# Board_Jam_v2.net
KiCad netlist of a schematic drawn in EAGLE
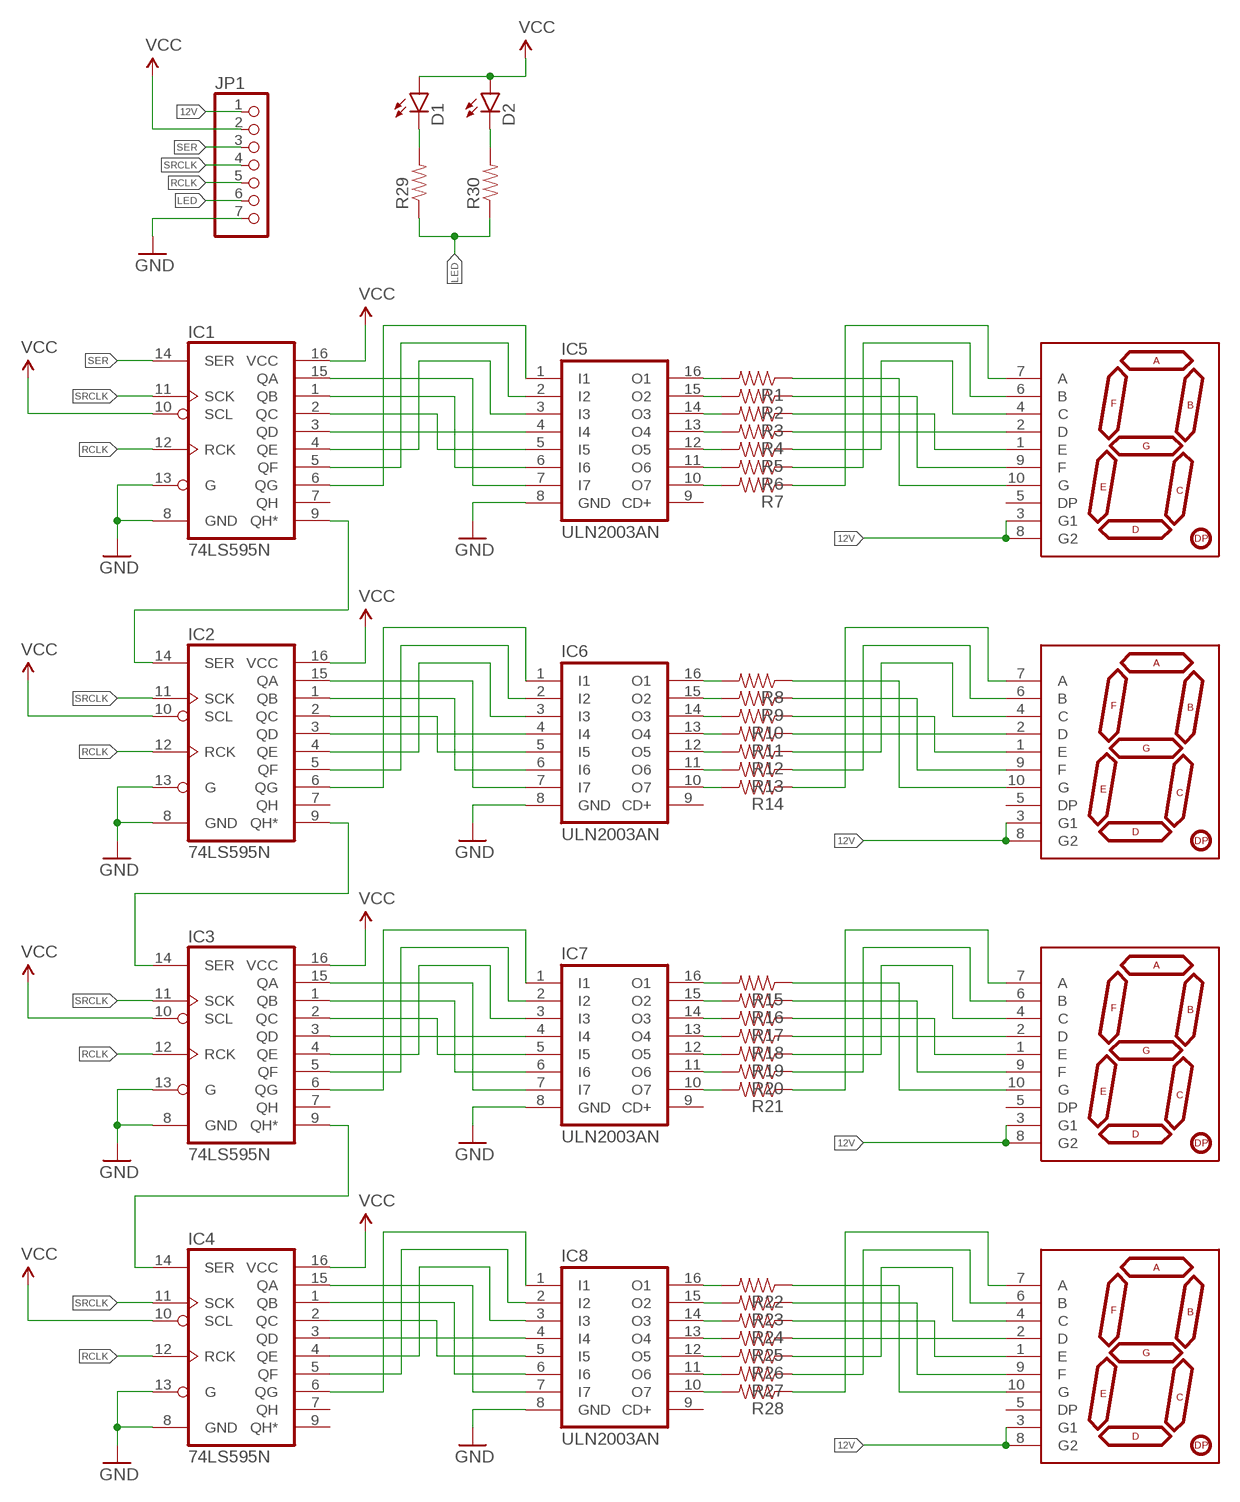
[diagram p0: schematic, sheet 1]

(export (version "E")
  (design (tool "Eeschema 10.0.6"))
  (components
    (comp (ref "D1")
      (value "LED5MM")
      (footprint "eagle-import:LED5MM")
      (libsource (lib "eagle-import") (part "LED5MM"))
    )
    (comp (ref "D2")
      (value "LED5MM")
      (footprint "eagle-import:LED5MM")
      (libsource (lib "eagle-import") (part "LED5MM"))
    )
    (comp (ref "IC1")
      (value "74LS595N")
      (footprint "eagle-import:DIL16")
      (libsource (lib "eagle-import") (part "74595NLS"))
    )
    (comp (ref "IC2")
      (value "74LS595N")
      (footprint "eagle-import:DIL16")
      (libsource (lib "eagle-import") (part "74595NLS"))
    )
    (comp (ref "IC3")
      (value "74LS595N")
      (footprint "eagle-import:DIL16")
      (libsource (lib "eagle-import") (part "74595NLS"))
    )
    (comp (ref "IC4")
      (value "74LS595N")
      (footprint "eagle-import:DIL16")
      (libsource (lib "eagle-import") (part "74595NLS"))
    )
    (comp (ref "IC5")
      (value "ULN2003AN")
      (footprint "eagle-import:DIL16")
      (libsource (lib "eagle-import") (part "ULN2003AN"))
    )
    (comp (ref "IC6")
      (value "ULN2003AN")
      (footprint "eagle-import:DIL16")
      (libsource (lib "eagle-import") (part "ULN2003AN"))
    )
    (comp (ref "IC7")
      (value "ULN2003AN")
      (footprint "eagle-import:DIL16")
      (libsource (lib "eagle-import") (part "ULN2003AN"))
    )
    (comp (ref "IC8")
      (value "ULN2003AN")
      (footprint "eagle-import:DIL16")
      (libsource (lib "eagle-import") (part "ULN2003AN"))
    )
    (comp (ref "JP1")
      (value "PINHD-1X7")
      (footprint "eagle-import:1X07")
      (libsource (lib "eagle-import") (part "PINHD-1X7"))
    )
    (comp (ref "R1")
      (value "RESISTORPTH-1/4W")
      (footprint "eagle-import:AXIAL-0.4")
      (libsource (lib "eagle-import") (part "RESISTORPTH-1/4W"))
    )
    (comp (ref "R2")
      (value "RESISTORPTH-1/4W")
      (footprint "eagle-import:AXIAL-0.4")
      (libsource (lib "eagle-import") (part "RESISTORPTH-1/4W"))
    )
    (comp (ref "R3")
      (value "RESISTORPTH-1/4W")
      (footprint "eagle-import:AXIAL-0.4")
      (libsource (lib "eagle-import") (part "RESISTORPTH-1/4W"))
    )
    (comp (ref "R4")
      (value "RESISTORPTH-1/4W")
      (footprint "eagle-import:AXIAL-0.4")
      (libsource (lib "eagle-import") (part "RESISTORPTH-1/4W"))
    )
    (comp (ref "R5")
      (value "RESISTORPTH-1/4W")
      (footprint "eagle-import:AXIAL-0.4")
      (libsource (lib "eagle-import") (part "RESISTORPTH-1/4W"))
    )
    (comp (ref "R6")
      (value "RESISTORPTH-1/4W")
      (footprint "eagle-import:AXIAL-0.4")
      (libsource (lib "eagle-import") (part "RESISTORPTH-1/4W"))
    )
    (comp (ref "R7")
      (value "RESISTORPTH-1/4W")
      (footprint "eagle-import:AXIAL-0.4")
      (libsource (lib "eagle-import") (part "RESISTORPTH-1/4W"))
    )
    (comp (ref "R8")
      (value "RESISTORPTH-1/4W")
      (footprint "eagle-import:AXIAL-0.4")
      (libsource (lib "eagle-import") (part "RESISTORPTH-1/4W"))
    )
    (comp (ref "R9")
      (value "RESISTORPTH-1/4W")
      (footprint "eagle-import:AXIAL-0.4")
      (libsource (lib "eagle-import") (part "RESISTORPTH-1/4W"))
    )
    (comp (ref "R10")
      (value "RESISTORPTH-1/4W")
      (footprint "eagle-import:AXIAL-0.4")
      (libsource (lib "eagle-import") (part "RESISTORPTH-1/4W"))
    )
    (comp (ref "R11")
      (value "RESISTORPTH-1/4W")
      (footprint "eagle-import:AXIAL-0.4")
      (libsource (lib "eagle-import") (part "RESISTORPTH-1/4W"))
    )
    (comp (ref "R12")
      (value "RESISTORPTH-1/4W")
      (footprint "eagle-import:AXIAL-0.4")
      (libsource (lib "eagle-import") (part "RESISTORPTH-1/4W"))
    )
    (comp (ref "R13")
      (value "RESISTORPTH-1/4W")
      (footprint "eagle-import:AXIAL-0.4")
      (libsource (lib "eagle-import") (part "RESISTORPTH-1/4W"))
    )
    (comp (ref "R14")
      (value "RESISTORPTH-1/4W")
      (footprint "eagle-import:AXIAL-0.4")
      (libsource (lib "eagle-import") (part "RESISTORPTH-1/4W"))
    )
    (comp (ref "R15")
      (value "RESISTORPTH-1/4W")
      (footprint "eagle-import:AXIAL-0.4")
      (libsource (lib "eagle-import") (part "RESISTORPTH-1/4W"))
    )
    (comp (ref "R16")
      (value "RESISTORPTH-1/4W")
      (footprint "eagle-import:AXIAL-0.4")
      (libsource (lib "eagle-import") (part "RESISTORPTH-1/4W"))
    )
    (comp (ref "R17")
      (value "RESISTORPTH-1/4W")
      (footprint "eagle-import:AXIAL-0.4")
      (libsource (lib "eagle-import") (part "RESISTORPTH-1/4W"))
    )
    (comp (ref "R18")
      (value "RESISTORPTH-1/4W")
      (footprint "eagle-import:AXIAL-0.4")
      (libsource (lib "eagle-import") (part "RESISTORPTH-1/4W"))
    )
    (comp (ref "R19")
      (value "RESISTORPTH-1/4W")
      (footprint "eagle-import:AXIAL-0.4")
      (libsource (lib "eagle-import") (part "RESISTORPTH-1/4W"))
    )
    (comp (ref "R20")
      (value "RESISTORPTH-1/4W")
      (footprint "eagle-import:AXIAL-0.4")
      (libsource (lib "eagle-import") (part "RESISTORPTH-1/4W"))
    )
    (comp (ref "R21")
      (value "RESISTORPTH-1/4W")
      (footprint "eagle-import:AXIAL-0.4")
      (libsource (lib "eagle-import") (part "RESISTORPTH-1/4W"))
    )
    (comp (ref "R22")
      (value "RESISTORPTH-1/4W")
      (footprint "eagle-import:AXIAL-0.4")
      (libsource (lib "eagle-import") (part "RESISTORPTH-1/4W"))
    )
    (comp (ref "R23")
      (value "RESISTORPTH-1/4W")
      (footprint "eagle-import:AXIAL-0.4")
      (libsource (lib "eagle-import") (part "RESISTORPTH-1/4W"))
    )
    (comp (ref "R24")
      (value "RESISTORPTH-1/4W")
      (footprint "eagle-import:AXIAL-0.4")
      (libsource (lib "eagle-import") (part "RESISTORPTH-1/4W"))
    )
    (comp (ref "R25")
      (value "RESISTORPTH-1/4W")
      (footprint "eagle-import:AXIAL-0.4")
      (libsource (lib "eagle-import") (part "RESISTORPTH-1/4W"))
    )
    (comp (ref "R26")
      (value "RESISTORPTH-1/4W")
      (footprint "eagle-import:AXIAL-0.4")
      (libsource (lib "eagle-import") (part "RESISTORPTH-1/4W"))
    )
    (comp (ref "R27")
      (value "RESISTORPTH-1/4W")
      (footprint "eagle-import:AXIAL-0.4")
      (libsource (lib "eagle-import") (part "RESISTORPTH-1/4W"))
    )
    (comp (ref "R28")
      (value "RESISTORPTH-1/4W")
      (footprint "eagle-import:AXIAL-0.4")
      (libsource (lib "eagle-import") (part "RESISTORPTH-1/4W"))
    )
    (comp (ref "R29")
      (value "RESISTORPTH-1/4W")
      (footprint "eagle-import:AXIAL-0.4")
      (libsource (lib "eagle-import") (part "RESISTORPTH-1/4W"))
    )
    (comp (ref "R30")
      (value "RESISTORPTH-1/4W")
      (footprint "eagle-import:AXIAL-0.4")
      (libsource (lib "eagle-import") (part "RESISTORPTH-1/4W"))
    )
    (comp (ref "U$1")
      (value "7-SEGMENT-DISPLAY-1\"-RED7-SEGMENT-1.8\"PTH")
      (footprint "eagle-import:7-SEGMENT-1_PTH")
      (libsource (lib "eagle-import") (part "7-SEGMENT-DISPLAY-1{dblquote}-RED7-SEGMENT-1.8{dblquote}PTH"))
    )
    (comp (ref "U$2")
      (value "7-SEGMENT-DISPLAY-1\"-RED7-SEGMENT-1.8\"PTH")
      (footprint "eagle-import:7-SEGMENT-1_PTH")
      (libsource (lib "eagle-import") (part "7-SEGMENT-DISPLAY-1{dblquote}-RED7-SEGMENT-1.8{dblquote}PTH"))
    )
    (comp (ref "U$3")
      (value "7-SEGMENT-DISPLAY-1\"-RED7-SEGMENT-1.8\"PTH")
      (footprint "eagle-import:7-SEGMENT-1_PTH")
      (libsource (lib "eagle-import") (part "7-SEGMENT-DISPLAY-1{dblquote}-RED7-SEGMENT-1.8{dblquote}PTH"))
    )
    (comp (ref "U$4")
      (value "7-SEGMENT-DISPLAY-1\"-RED7-SEGMENT-1.8\"PTH")
      (footprint "eagle-import:7-SEGMENT-1_PTH")
      (libsource (lib "eagle-import") (part "7-SEGMENT-DISPLAY-1{dblquote}-RED7-SEGMENT-1.8{dblquote}PTH"))
    )
  )
  (nets
    (net (code "1") (name "12V") (class "Default")
      (node (ref "JP1") (pin "1") (pinfunction "1_1") (pintype "passive"))
      (node (ref "U$1") (pin "3") (pinfunction "G1_3") (pintype "bidirectional"))
      (node (ref "U$1") (pin "8") (pinfunction "G2_8") (pintype "bidirectional"))
      (node (ref "U$2") (pin "3") (pinfunction "G1_3") (pintype "bidirectional"))
      (node (ref "U$2") (pin "8") (pinfunction "G2_8") (pintype "bidirectional"))
      (node (ref "U$3") (pin "3") (pinfunction "G1_3") (pintype "bidirectional"))
      (node (ref "U$3") (pin "8") (pinfunction "G2_8") (pintype "bidirectional"))
      (node (ref "U$4") (pin "3") (pinfunction "G1_3") (pintype "bidirectional"))
      (node (ref "U$4") (pin "8") (pinfunction "G2_8") (pintype "bidirectional"))
    )
    (net (code "2") (name "GND") (class "Default")
      (node (ref "IC1") (pin "13") (pinfunction "G_13") (pintype "input"))
      (node (ref "IC1") (pin "8") (pinfunction "GND_8") (pintype "power_in"))
      (node (ref "IC2") (pin "13") (pinfunction "G_13") (pintype "input"))
      (node (ref "IC2") (pin "8") (pinfunction "GND_8") (pintype "power_in"))
      (node (ref "IC3") (pin "13") (pinfunction "G_13") (pintype "input"))
      (node (ref "IC3") (pin "8") (pinfunction "GND_8") (pintype "power_in"))
      (node (ref "IC4") (pin "13") (pinfunction "G_13") (pintype "input"))
      (node (ref "IC4") (pin "8") (pinfunction "GND_8") (pintype "power_in"))
      (node (ref "IC5") (pin "8") (pinfunction "GND_8") (pintype "power_in"))
      (node (ref "IC6") (pin "8") (pinfunction "GND_8") (pintype "power_in"))
      (node (ref "IC7") (pin "8") (pinfunction "GND_8") (pintype "power_in"))
      (node (ref "IC8") (pin "8") (pinfunction "GND_8") (pintype "power_in"))
      (node (ref "JP1") (pin "7") (pinfunction "7_7") (pintype "passive"))
    )
    (net (code "3") (name "LED") (class "Default")
      (node (ref "JP1") (pin "6") (pinfunction "6_6") (pintype "passive"))
      (node (ref "R29") (pin "P$1") (pinfunction "1_P$1") (pintype "passive"))
      (node (ref "R30") (pin "P$1") (pinfunction "1_P$1") (pintype "passive"))
    )
    (net (code "4") (name "Net-(D1-C)") (class "Default")
      (node (ref "D1") (pin "K") (pinfunction "C_K") (pintype "passive"))
      (node (ref "R29") (pin "P$2") (pinfunction "2_P$2") (pintype "passive"))
    )
    (net (code "5") (name "Net-(D2-C)") (class "Default")
      (node (ref "D2") (pin "K") (pinfunction "C_K") (pintype "passive"))
      (node (ref "R30") (pin "P$2") (pinfunction "2_P$2") (pintype "passive"))
    )
    (net (code "6") (name "Net-(IC1-QA)") (class "Default")
      (node (ref "IC1") (pin "15") (pinfunction "QA_15") (pintype "tri_state"))
      (node (ref "IC5") (pin "7") (pinfunction "I7_7") (pintype "input"))
    )
    (net (code "7") (name "Net-(IC1-QB)") (class "Default")
      (node (ref "IC1") (pin "1") (pinfunction "QB_1") (pintype "tri_state"))
      (node (ref "IC5") (pin "6") (pinfunction "I6_6") (pintype "input"))
    )
    (net (code "8") (name "Net-(IC1-QC)") (class "Default")
      (node (ref "IC1") (pin "2") (pinfunction "QC_2") (pintype "tri_state"))
      (node (ref "IC5") (pin "5") (pinfunction "I5_5") (pintype "input"))
    )
    (net (code "9") (name "Net-(IC1-QD)") (class "Default")
      (node (ref "IC1") (pin "3") (pinfunction "QD_3") (pintype "tri_state"))
      (node (ref "IC5") (pin "4") (pinfunction "I4_4") (pintype "input"))
    )
    (net (code "10") (name "Net-(IC1-QE)") (class "Default")
      (node (ref "IC1") (pin "4") (pinfunction "QE_4") (pintype "tri_state"))
      (node (ref "IC5") (pin "3") (pinfunction "I3_3") (pintype "input"))
    )
    (net (code "11") (name "Net-(IC1-QF)") (class "Default")
      (node (ref "IC1") (pin "5") (pinfunction "QF_5") (pintype "tri_state"))
      (node (ref "IC5") (pin "2") (pinfunction "I2_2") (pintype "input"))
    )
    (net (code "12") (name "Net-(IC1-QG)") (class "Default")
      (node (ref "IC1") (pin "6") (pinfunction "QG_6") (pintype "tri_state"))
      (node (ref "IC5") (pin "1") (pinfunction "I1_1") (pintype "input"))
    )
    (net (code "13") (name "Net-(IC1-QH*)") (class "Default")
      (node (ref "IC1") (pin "9") (pinfunction "QH*_9") (pintype "tri_state"))
      (node (ref "IC2") (pin "14") (pinfunction "SER_14") (pintype "input"))
    )
    (net (code "14") (name "Net-(IC2-QA)") (class "Default")
      (node (ref "IC2") (pin "15") (pinfunction "QA_15") (pintype "tri_state"))
      (node (ref "IC6") (pin "7") (pinfunction "I7_7") (pintype "input"))
    )
    (net (code "15") (name "Net-(IC2-QB)") (class "Default")
      (node (ref "IC2") (pin "1") (pinfunction "QB_1") (pintype "tri_state"))
      (node (ref "IC6") (pin "6") (pinfunction "I6_6") (pintype "input"))
    )
    (net (code "16") (name "Net-(IC2-QC)") (class "Default")
      (node (ref "IC2") (pin "2") (pinfunction "QC_2") (pintype "tri_state"))
      (node (ref "IC6") (pin "5") (pinfunction "I5_5") (pintype "input"))
    )
    (net (code "17") (name "Net-(IC2-QD)") (class "Default")
      (node (ref "IC2") (pin "3") (pinfunction "QD_3") (pintype "tri_state"))
      (node (ref "IC6") (pin "4") (pinfunction "I4_4") (pintype "input"))
    )
    (net (code "18") (name "Net-(IC2-QE)") (class "Default")
      (node (ref "IC2") (pin "4") (pinfunction "QE_4") (pintype "tri_state"))
      (node (ref "IC6") (pin "3") (pinfunction "I3_3") (pintype "input"))
    )
    (net (code "19") (name "Net-(IC2-QF)") (class "Default")
      (node (ref "IC2") (pin "5") (pinfunction "QF_5") (pintype "tri_state"))
      (node (ref "IC6") (pin "2") (pinfunction "I2_2") (pintype "input"))
    )
    (net (code "20") (name "Net-(IC2-QG)") (class "Default")
      (node (ref "IC2") (pin "6") (pinfunction "QG_6") (pintype "tri_state"))
      (node (ref "IC6") (pin "1") (pinfunction "I1_1") (pintype "input"))
    )
    (net (code "21") (name "Net-(IC2-QH*)") (class "Default")
      (node (ref "IC2") (pin "9") (pinfunction "QH*_9") (pintype "tri_state"))
      (node (ref "IC3") (pin "14") (pinfunction "SER_14") (pintype "input"))
    )
    (net (code "22") (name "Net-(IC3-QA)") (class "Default")
      (node (ref "IC3") (pin "15") (pinfunction "QA_15") (pintype "tri_state"))
      (node (ref "IC7") (pin "7") (pinfunction "I7_7") (pintype "input"))
    )
    (net (code "23") (name "Net-(IC3-QB)") (class "Default")
      (node (ref "IC3") (pin "1") (pinfunction "QB_1") (pintype "tri_state"))
      (node (ref "IC7") (pin "6") (pinfunction "I6_6") (pintype "input"))
    )
    (net (code "24") (name "Net-(IC3-QC)") (class "Default")
      (node (ref "IC3") (pin "2") (pinfunction "QC_2") (pintype "tri_state"))
      (node (ref "IC7") (pin "5") (pinfunction "I5_5") (pintype "input"))
    )
    (net (code "25") (name "Net-(IC3-QD)") (class "Default")
      (node (ref "IC3") (pin "3") (pinfunction "QD_3") (pintype "tri_state"))
      (node (ref "IC7") (pin "4") (pinfunction "I4_4") (pintype "input"))
    )
    (net (code "26") (name "Net-(IC3-QE)") (class "Default")
      (node (ref "IC3") (pin "4") (pinfunction "QE_4") (pintype "tri_state"))
      (node (ref "IC7") (pin "3") (pinfunction "I3_3") (pintype "input"))
    )
    (net (code "27") (name "Net-(IC3-QF)") (class "Default")
      (node (ref "IC3") (pin "5") (pinfunction "QF_5") (pintype "tri_state"))
      (node (ref "IC7") (pin "2") (pinfunction "I2_2") (pintype "input"))
    )
    (net (code "28") (name "Net-(IC3-QG)") (class "Default")
      (node (ref "IC3") (pin "6") (pinfunction "QG_6") (pintype "tri_state"))
      (node (ref "IC7") (pin "1") (pinfunction "I1_1") (pintype "input"))
    )
    (net (code "29") (name "Net-(IC3-QH*)") (class "Default")
      (node (ref "IC3") (pin "9") (pinfunction "QH*_9") (pintype "tri_state"))
      (node (ref "IC4") (pin "14") (pinfunction "SER_14") (pintype "input"))
    )
    (net (code "30") (name "Net-(IC4-QA)") (class "Default")
      (node (ref "IC4") (pin "15") (pinfunction "QA_15") (pintype "tri_state"))
      (node (ref "IC8") (pin "7") (pinfunction "I7_7") (pintype "input"))
    )
    (net (code "31") (name "Net-(IC4-QB)") (class "Default")
      (node (ref "IC4") (pin "1") (pinfunction "QB_1") (pintype "tri_state"))
      (node (ref "IC8") (pin "6") (pinfunction "I6_6") (pintype "input"))
    )
    (net (code "32") (name "Net-(IC4-QC)") (class "Default")
      (node (ref "IC4") (pin "2") (pinfunction "QC_2") (pintype "tri_state"))
      (node (ref "IC8") (pin "5") (pinfunction "I5_5") (pintype "input"))
    )
    (net (code "33") (name "Net-(IC4-QD)") (class "Default")
      (node (ref "IC4") (pin "3") (pinfunction "QD_3") (pintype "tri_state"))
      (node (ref "IC8") (pin "4") (pinfunction "I4_4") (pintype "input"))
    )
    (net (code "34") (name "Net-(IC4-QE)") (class "Default")
      (node (ref "IC4") (pin "4") (pinfunction "QE_4") (pintype "tri_state"))
      (node (ref "IC8") (pin "3") (pinfunction "I3_3") (pintype "input"))
    )
    (net (code "35") (name "Net-(IC4-QF)") (class "Default")
      (node (ref "IC4") (pin "5") (pinfunction "QF_5") (pintype "tri_state"))
      (node (ref "IC8") (pin "2") (pinfunction "I2_2") (pintype "input"))
    )
    (net (code "36") (name "Net-(IC4-QG)") (class "Default")
      (node (ref "IC4") (pin "6") (pinfunction "QG_6") (pintype "tri_state"))
      (node (ref "IC8") (pin "1") (pinfunction "I1_1") (pintype "input"))
    )
    (net (code "37") (name "Net-(IC5-O1)") (class "Default")
      (node (ref "IC5") (pin "16") (pinfunction "O1_16") (pintype "open_collector"))
      (node (ref "R1") (pin "P$2") (pinfunction "2_P$2") (pintype "passive"))
    )
    (net (code "38") (name "Net-(IC5-O2)") (class "Default")
      (node (ref "IC5") (pin "15") (pinfunction "O2_15") (pintype "open_collector"))
      (node (ref "R2") (pin "P$2") (pinfunction "2_P$2") (pintype "passive"))
    )
    (net (code "39") (name "Net-(IC5-O3)") (class "Default")
      (node (ref "IC5") (pin "14") (pinfunction "O3_14") (pintype "open_collector"))
      (node (ref "R3") (pin "P$2") (pinfunction "2_P$2") (pintype "passive"))
    )
    (net (code "40") (name "Net-(IC5-O4)") (class "Default")
      (node (ref "IC5") (pin "13") (pinfunction "O4_13") (pintype "open_collector"))
      (node (ref "R4") (pin "P$2") (pinfunction "2_P$2") (pintype "passive"))
    )
    (net (code "41") (name "Net-(IC5-O5)") (class "Default")
      (node (ref "IC5") (pin "12") (pinfunction "O5_12") (pintype "open_collector"))
      (node (ref "R5") (pin "P$2") (pinfunction "2_P$2") (pintype "passive"))
    )
    (net (code "42") (name "Net-(IC5-O6)") (class "Default")
      (node (ref "IC5") (pin "11") (pinfunction "O6_11") (pintype "open_collector"))
      (node (ref "R6") (pin "P$2") (pinfunction "2_P$2") (pintype "passive"))
    )
    (net (code "43") (name "Net-(IC5-O7)") (class "Default")
      (node (ref "IC5") (pin "10") (pinfunction "O7_10") (pintype "open_collector"))
      (node (ref "R7") (pin "P$2") (pinfunction "2_P$2") (pintype "passive"))
    )
    (net (code "44") (name "Net-(IC6-O1)") (class "Default")
      (node (ref "IC6") (pin "16") (pinfunction "O1_16") (pintype "open_collector"))
      (node (ref "R8") (pin "P$2") (pinfunction "2_P$2") (pintype "passive"))
    )
    (net (code "45") (name "Net-(IC6-O2)") (class "Default")
      (node (ref "IC6") (pin "15") (pinfunction "O2_15") (pintype "open_collector"))
      (node (ref "R9") (pin "P$2") (pinfunction "2_P$2") (pintype "passive"))
    )
    (net (code "46") (name "Net-(IC6-O3)") (class "Default")
      (node (ref "IC6") (pin "14") (pinfunction "O3_14") (pintype "open_collector"))
      (node (ref "R10") (pin "P$2") (pinfunction "2_P$2") (pintype "passive"))
    )
    (net (code "47") (name "Net-(IC6-O4)") (class "Default")
      (node (ref "IC6") (pin "13") (pinfunction "O4_13") (pintype "open_collector"))
      (node (ref "R11") (pin "P$2") (pinfunction "2_P$2") (pintype "passive"))
    )
    (net (code "48") (name "Net-(IC6-O5)") (class "Default")
      (node (ref "IC6") (pin "12") (pinfunction "O5_12") (pintype "open_collector"))
      (node (ref "R12") (pin "P$2") (pinfunction "2_P$2") (pintype "passive"))
    )
    (net (code "49") (name "Net-(IC6-O6)") (class "Default")
      (node (ref "IC6") (pin "11") (pinfunction "O6_11") (pintype "open_collector"))
      (node (ref "R13") (pin "P$2") (pinfunction "2_P$2") (pintype "passive"))
    )
    (net (code "50") (name "Net-(IC6-O7)") (class "Default")
      (node (ref "IC6") (pin "10") (pinfunction "O7_10") (pintype "open_collector"))
      (node (ref "R14") (pin "P$2") (pinfunction "2_P$2") (pintype "passive"))
    )
    (net (code "51") (name "Net-(IC7-O1)") (class "Default")
      (node (ref "IC7") (pin "16") (pinfunction "O1_16") (pintype "open_collector"))
      (node (ref "R15") (pin "P$2") (pinfunction "2_P$2") (pintype "passive"))
    )
    (net (code "52") (name "Net-(IC7-O2)") (class "Default")
      (node (ref "IC7") (pin "15") (pinfunction "O2_15") (pintype "open_collector"))
      (node (ref "R16") (pin "P$2") (pinfunction "2_P$2") (pintype "passive"))
    )
    (net (code "53") (name "Net-(IC7-O3)") (class "Default")
      (node (ref "IC7") (pin "14") (pinfunction "O3_14") (pintype "open_collector"))
      (node (ref "R17") (pin "P$2") (pinfunction "2_P$2") (pintype "passive"))
    )
    (net (code "54") (name "Net-(IC7-O4)") (class "Default")
      (node (ref "IC7") (pin "13") (pinfunction "O4_13") (pintype "open_collector"))
      (node (ref "R18") (pin "P$2") (pinfunction "2_P$2") (pintype "passive"))
    )
    (net (code "55") (name "Net-(IC7-O5)") (class "Default")
      (node (ref "IC7") (pin "12") (pinfunction "O5_12") (pintype "open_collector"))
      (node (ref "R19") (pin "P$2") (pinfunction "2_P$2") (pintype "passive"))
    )
    (net (code "56") (name "Net-(IC7-O6)") (class "Default")
      (node (ref "IC7") (pin "11") (pinfunction "O6_11") (pintype "open_collector"))
      (node (ref "R20") (pin "P$2") (pinfunction "2_P$2") (pintype "passive"))
    )
    (net (code "57") (name "Net-(IC7-O7)") (class "Default")
      (node (ref "IC7") (pin "10") (pinfunction "O7_10") (pintype "open_collector"))
      (node (ref "R21") (pin "P$2") (pinfunction "2_P$2") (pintype "passive"))
    )
    (net (code "58") (name "Net-(IC8-O1)") (class "Default")
      (node (ref "IC8") (pin "16") (pinfunction "O1_16") (pintype "open_collector"))
      (node (ref "R22") (pin "P$2") (pinfunction "2_P$2") (pintype "passive"))
    )
    (net (code "59") (name "Net-(IC8-O2)") (class "Default")
      (node (ref "IC8") (pin "15") (pinfunction "O2_15") (pintype "open_collector"))
      (node (ref "R23") (pin "P$2") (pinfunction "2_P$2") (pintype "passive"))
    )
    (net (code "60") (name "Net-(IC8-O3)") (class "Default")
      (node (ref "IC8") (pin "14") (pinfunction "O3_14") (pintype "open_collector"))
      (node (ref "R24") (pin "P$2") (pinfunction "2_P$2") (pintype "passive"))
    )
    (net (code "61") (name "Net-(IC8-O4)") (class "Default")
      (node (ref "IC8") (pin "13") (pinfunction "O4_13") (pintype "open_collector"))
      (node (ref "R25") (pin "P$2") (pinfunction "2_P$2") (pintype "passive"))
    )
    (net (code "62") (name "Net-(IC8-O5)") (class "Default")
      (node (ref "IC8") (pin "12") (pinfunction "O5_12") (pintype "open_collector"))
      (node (ref "R26") (pin "P$2") (pinfunction "2_P$2") (pintype "passive"))
    )
    (net (code "63") (name "Net-(IC8-O6)") (class "Default")
      (node (ref "IC8") (pin "11") (pinfunction "O6_11") (pintype "open_collector"))
      (node (ref "R27") (pin "P$2") (pinfunction "2_P$2") (pintype "passive"))
    )
    (net (code "64") (name "Net-(IC8-O7)") (class "Default")
      (node (ref "IC8") (pin "10") (pinfunction "O7_10") (pintype "open_collector"))
      (node (ref "R28") (pin "P$2") (pinfunction "2_P$2") (pintype "passive"))
    )
    (net (code "65") (name "Net-(R1-1)") (class "Default")
      (node (ref "R1") (pin "P$1") (pinfunction "1_P$1") (pintype "passive"))
      (node (ref "U$1") (pin "10") (pinfunction "G_10") (pintype "bidirectional"))
    )
    (net (code "66") (name "Net-(R2-1)") (class "Default")
      (node (ref "R2") (pin "P$1") (pinfunction "1_P$1") (pintype "passive"))
      (node (ref "U$1") (pin "9") (pinfunction "F_9") (pintype "bidirectional"))
    )
    (net (code "67") (name "Net-(R3-1)") (class "Default")
      (node (ref "R3") (pin "P$1") (pinfunction "1_P$1") (pintype "passive"))
      (node (ref "U$1") (pin "1") (pinfunction "E_1") (pintype "bidirectional"))
    )
    (net (code "68") (name "Net-(R4-1)") (class "Default")
      (node (ref "R4") (pin "P$1") (pinfunction "1_P$1") (pintype "passive"))
      (node (ref "U$1") (pin "2") (pinfunction "D_2") (pintype "bidirectional"))
    )
    (net (code "69") (name "Net-(R5-1)") (class "Default")
      (node (ref "R5") (pin "P$1") (pinfunction "1_P$1") (pintype "passive"))
      (node (ref "U$1") (pin "4") (pinfunction "C_4") (pintype "bidirectional"))
    )
    (net (code "70") (name "Net-(R6-1)") (class "Default")
      (node (ref "R6") (pin "P$1") (pinfunction "1_P$1") (pintype "passive"))
      (node (ref "U$1") (pin "6") (pinfunction "B_6") (pintype "bidirectional"))
    )
    (net (code "71") (name "Net-(R7-1)") (class "Default")
      (node (ref "R7") (pin "P$1") (pinfunction "1_P$1") (pintype "passive"))
      (node (ref "U$1") (pin "7") (pinfunction "A_7") (pintype "bidirectional"))
    )
    (net (code "72") (name "Net-(R8-1)") (class "Default")
      (node (ref "R8") (pin "P$1") (pinfunction "1_P$1") (pintype "passive"))
      (node (ref "U$2") (pin "10") (pinfunction "G_10") (pintype "bidirectional"))
    )
    (net (code "73") (name "Net-(R9-1)") (class "Default")
      (node (ref "R9") (pin "P$1") (pinfunction "1_P$1") (pintype "passive"))
      (node (ref "U$2") (pin "9") (pinfunction "F_9") (pintype "bidirectional"))
    )
    (net (code "74") (name "Net-(R10-1)") (class "Default")
      (node (ref "R10") (pin "P$1") (pinfunction "1_P$1") (pintype "passive"))
      (node (ref "U$2") (pin "1") (pinfunction "E_1") (pintype "bidirectional"))
    )
    (net (code "75") (name "Net-(R11-1)") (class "Default")
      (node (ref "R11") (pin "P$1") (pinfunction "1_P$1") (pintype "passive"))
      (node (ref "U$2") (pin "2") (pinfunction "D_2") (pintype "bidirectional"))
    )
    (net (code "76") (name "Net-(R12-1)") (class "Default")
      (node (ref "R12") (pin "P$1") (pinfunction "1_P$1") (pintype "passive"))
      (node (ref "U$2") (pin "4") (pinfunction "C_4") (pintype "bidirectional"))
    )
    (net (code "77") (name "Net-(R13-1)") (class "Default")
      (node (ref "R13") (pin "P$1") (pinfunction "1_P$1") (pintype "passive"))
      (node (ref "U$2") (pin "6") (pinfunction "B_6") (pintype "bidirectional"))
    )
    (net (code "78") (name "Net-(R14-1)") (class "Default")
      (node (ref "R14") (pin "P$1") (pinfunction "1_P$1") (pintype "passive"))
      (node (ref "U$2") (pin "7") (pinfunction "A_7") (pintype "bidirectional"))
    )
    (net (code "79") (name "Net-(R15-1)") (class "Default")
      (node (ref "R15") (pin "P$1") (pinfunction "1_P$1") (pintype "passive"))
      (node (ref "U$3") (pin "10") (pinfunction "G_10") (pintype "bidirectional"))
    )
    (net (code "80") (name "Net-(R16-1)") (class "Default")
      (node (ref "R16") (pin "P$1") (pinfunction "1_P$1") (pintype "passive"))
      (node (ref "U$3") (pin "9") (pinfunction "F_9") (pintype "bidirectional"))
    )
    (net (code "81") (name "Net-(R17-1)") (class "Default")
      (node (ref "R17") (pin "P$1") (pinfunction "1_P$1") (pintype "passive"))
      (node (ref "U$3") (pin "1") (pinfunction "E_1") (pintype "bidirectional"))
    )
    (net (code "82") (name "Net-(R18-1)") (class "Default")
      (node (ref "R18") (pin "P$1") (pinfunction "1_P$1") (pintype "passive"))
      (node (ref "U$3") (pin "2") (pinfunction "D_2") (pintype "bidirectional"))
    )
    (net (code "83") (name "Net-(R19-1)") (class "Default")
      (node (ref "R19") (pin "P$1") (pinfunction "1_P$1") (pintype "passive"))
      (node (ref "U$3") (pin "4") (pinfunction "C_4") (pintype "bidirectional"))
    )
    (net (code "84") (name "Net-(R20-1)") (class "Default")
      (node (ref "R20") (pin "P$1") (pinfunction "1_P$1") (pintype "passive"))
      (node (ref "U$3") (pin "6") (pinfunction "B_6") (pintype "bidirectional"))
    )
    (net (code "85") (name "Net-(R21-1)") (class "Default")
      (node (ref "R21") (pin "P$1") (pinfunction "1_P$1") (pintype "passive"))
      (node (ref "U$3") (pin "7") (pinfunction "A_7") (pintype "bidirectional"))
    )
    (net (code "86") (name "Net-(R22-1)") (class "Default")
      (node (ref "R22") (pin "P$1") (pinfunction "1_P$1") (pintype "passive"))
      (node (ref "U$4") (pin "10") (pinfunction "G_10") (pintype "bidirectional"))
    )
    (net (code "87") (name "Net-(R23-1)") (class "Default")
      (node (ref "R23") (pin "P$1") (pinfunction "1_P$1") (pintype "passive"))
      (node (ref "U$4") (pin "9") (pinfunction "F_9") (pintype "bidirectional"))
    )
    (net (code "88") (name "Net-(R24-1)") (class "Default")
      (node (ref "R24") (pin "P$1") (pinfunction "1_P$1") (pintype "passive"))
      (node (ref "U$4") (pin "1") (pinfunction "E_1") (pintype "bidirectional"))
    )
    (net (code "89") (name "Net-(R25-1)") (class "Default")
      (node (ref "R25") (pin "P$1") (pinfunction "1_P$1") (pintype "passive"))
      (node (ref "U$4") (pin "2") (pinfunction "D_2") (pintype "bidirectional"))
    )
    (net (code "90") (name "Net-(R26-1)") (class "Default")
      (node (ref "R26") (pin "P$1") (pinfunction "1_P$1") (pintype "passive"))
      (node (ref "U$4") (pin "4") (pinfunction "C_4") (pintype "bidirectional"))
    )
    (net (code "91") (name "Net-(R27-1)") (class "Default")
      (node (ref "R27") (pin "P$1") (pinfunction "1_P$1") (pintype "passive"))
      (node (ref "U$4") (pin "6") (pinfunction "B_6") (pintype "bidirectional"))
    )
    (net (code "92") (name "Net-(R28-1)") (class "Default")
      (node (ref "R28") (pin "P$1") (pinfunction "1_P$1") (pintype "passive"))
      (node (ref "U$4") (pin "7") (pinfunction "A_7") (pintype "bidirectional"))
    )
    (net (code "93") (name "RCLK") (class "Default")
      (node (ref "IC1") (pin "12") (pinfunction "RCK_12") (pintype "input"))
      (node (ref "IC2") (pin "12") (pinfunction "RCK_12") (pintype "input"))
      (node (ref "IC3") (pin "12") (pinfunction "RCK_12") (pintype "input"))
      (node (ref "IC4") (pin "12") (pinfunction "RCK_12") (pintype "input"))
      (node (ref "JP1") (pin "5") (pinfunction "5_5") (pintype "passive"))
    )
    (net (code "94") (name "SER") (class "Default")
      (node (ref "IC1") (pin "14") (pinfunction "SER_14") (pintype "input"))
      (node (ref "JP1") (pin "3") (pinfunction "3_3") (pintype "passive"))
    )
    (net (code "95") (name "SRCLK") (class "Default")
      (node (ref "IC1") (pin "11") (pinfunction "SCK_11") (pintype "input"))
      (node (ref "IC2") (pin "11") (pinfunction "SCK_11") (pintype "input"))
      (node (ref "IC3") (pin "11") (pinfunction "SCK_11") (pintype "input"))
      (node (ref "IC4") (pin "11") (pinfunction "SCK_11") (pintype "input"))
      (node (ref "JP1") (pin "4") (pinfunction "4_4") (pintype "passive"))
    )
    (net (code "96") (name "VCC") (class "Default")
      (node (ref "D1") (pin "A") (pinfunction "A_A") (pintype "passive"))
      (node (ref "D2") (pin "A") (pinfunction "A_A") (pintype "passive"))
      (node (ref "IC1") (pin "10") (pinfunction "SCL_10") (pintype "input"))
      (node (ref "IC1") (pin "16") (pinfunction "VCC_16") (pintype "power_in"))
      (node (ref "IC2") (pin "10") (pinfunction "SCL_10") (pintype "input"))
      (node (ref "IC2") (pin "16") (pinfunction "VCC_16") (pintype "power_in"))
      (node (ref "IC3") (pin "10") (pinfunction "SCL_10") (pintype "input"))
      (node (ref "IC3") (pin "16") (pinfunction "VCC_16") (pintype "power_in"))
      (node (ref "IC4") (pin "10") (pinfunction "SCL_10") (pintype "input"))
      (node (ref "IC4") (pin "16") (pinfunction "VCC_16") (pintype "power_in"))
      (node (ref "JP1") (pin "2") (pinfunction "2_2") (pintype "passive"))
    )
    (net (code "97") (name "unconnected-(IC1-QH-Pad7)") (class "Default")
      (node (ref "IC1") (pin "7") (pinfunction "QH_7") (pintype "tri_state"))
    )
    (net (code "98") (name "unconnected-(IC2-QH-Pad7)") (class "Default")
      (node (ref "IC2") (pin "7") (pinfunction "QH_7") (pintype "tri_state"))
    )
    (net (code "99") (name "unconnected-(IC3-QH-Pad7)") (class "Default")
      (node (ref "IC3") (pin "7") (pinfunction "QH_7") (pintype "tri_state"))
    )
    (net (code "100") (name "unconnected-(IC4-QH*-Pad9)") (class "Default")
      (node (ref "IC4") (pin "9") (pinfunction "QH*_9") (pintype "tri_state"))
    )
    (net (code "101") (name "unconnected-(IC4-QH-Pad7)") (class "Default")
      (node (ref "IC4") (pin "7") (pinfunction "QH_7") (pintype "tri_state"))
    )
    (net (code "102") (name "unconnected-(IC5-CD+-Pad9)") (class "Default")
      (node (ref "IC5") (pin "9") (pinfunction "CD+_9") (pintype "passive"))
    )
    (net (code "103") (name "unconnected-(IC6-CD+-Pad9)") (class "Default")
      (node (ref "IC6") (pin "9") (pinfunction "CD+_9") (pintype "passive"))
    )
    (net (code "104") (name "unconnected-(IC7-CD+-Pad9)") (class "Default")
      (node (ref "IC7") (pin "9") (pinfunction "CD+_9") (pintype "passive"))
    )
    (net (code "105") (name "unconnected-(IC8-CD+-Pad9)") (class "Default")
      (node (ref "IC8") (pin "9") (pinfunction "CD+_9") (pintype "passive"))
    )
    (net (code "106") (name "unconnected-(U$1-DP-Pad5)") (class "Default")
      (node (ref "U$1") (pin "5") (pinfunction "DP_5") (pintype "bidirectional"))
    )
    (net (code "107") (name "unconnected-(U$2-DP-Pad5)") (class "Default")
      (node (ref "U$2") (pin "5") (pinfunction "DP_5") (pintype "bidirectional"))
    )
    (net (code "108") (name "unconnected-(U$3-DP-Pad5)") (class "Default")
      (node (ref "U$3") (pin "5") (pinfunction "DP_5") (pintype "bidirectional"))
    )
    (net (code "109") (name "unconnected-(U$4-DP-Pad5)") (class "Default")
      (node (ref "U$4") (pin "5") (pinfunction "DP_5") (pintype "bidirectional"))
    )
  )
)
